# GeckoBreakout.net
KiCad netlist of a schematic drawn in Altium Designer
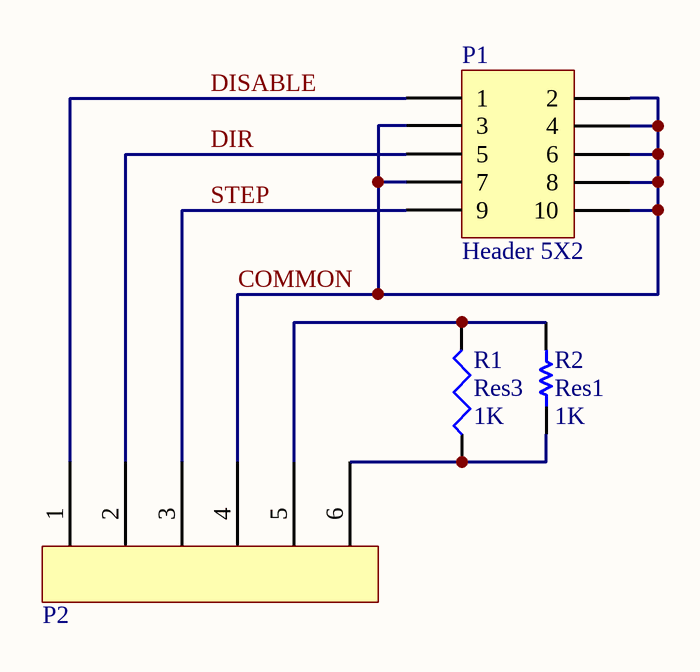
[diagram p0: GeckoBreakout.SchDoc]

(export (version "E")
  (design (tool "Eeschema 10.0.6"))
  (components
    (comp (ref "P1")
      (value "Header 5X2")
      (footprint "BETTER HDR2X5")
      (description "Header, 5-Pin, Dual row")
      (fields (field (name "PUBLISHER") "Altium Limited"))
      (libsource (lib "Miscellaneous Connectors") (part "Header 5X2"))
    )
    (comp (ref "P2")
      (value "Phoenix_1933228")
      (footprint "Phoenix_1933228")
      (libsource (lib "GechoBreakout") (part "Phoenix_1933228"))
    )
    (comp (ref "R1")
      (value "Res3")
      (footprint "3216[1206]")
      (description "Resistor")
      (fields (field (name "ALTIUM_VALUE") "1K") (field (name "PUBLISHER") "Altium Limited"))
      (libsource (lib "Miscellaneous Devices") (part "Res3"))
    )
    (comp (ref "R2")
      (value "Res1")
      (footprint "AXIAL-0.4")
      (description "Resistor")
      (fields (field (name "ALTIUM_VALUE") "1K") (field (name "PUBLISHER") "Altium Limited"))
      (libsource (lib "Miscellaneous Devices") (part "Res1"))
    )
  )
  (nets
    (net (code "1") (name "/COMMON") (class "Default")
      (node (ref "P1") (pin "10") (pinfunction "10_10") (pintype "passive"))
      (node (ref "P1") (pin "2") (pinfunction "2_2") (pintype "passive"))
      (node (ref "P1") (pin "3") (pinfunction "3_3") (pintype "passive"))
      (node (ref "P1") (pin "4") (pinfunction "4_4") (pintype "passive"))
      (node (ref "P1") (pin "6") (pinfunction "6_6") (pintype "passive"))
      (node (ref "P1") (pin "7") (pinfunction "7_7") (pintype "passive"))
      (node (ref "P1") (pin "8") (pinfunction "8_8") (pintype "passive"))
      (node (ref "P2") (pin "4") (pinfunction "4_4") (pintype "passive"))
    )
    (net (code "2") (name "/DIR") (class "Default")
      (node (ref "P1") (pin "5") (pinfunction "5_5") (pintype "passive"))
      (node (ref "P2") (pin "2") (pinfunction "2_2") (pintype "passive"))
    )
    (net (code "3") (name "/DISABLE") (class "Default")
      (node (ref "P1") (pin "1") (pinfunction "1_1") (pintype "passive"))
      (node (ref "P2") (pin "1") (pinfunction "1_1") (pintype "passive"))
    )
    (net (code "4") (name "/STEP") (class "Default")
      (node (ref "P1") (pin "9") (pinfunction "9_9") (pintype "passive"))
      (node (ref "P2") (pin "3") (pinfunction "3_3") (pintype "passive"))
    )
    (net (code "5") (name "Net-(P2-Pad5)") (class "Default")
      (node (ref "P2") (pin "5") (pinfunction "5_5") (pintype "passive"))
      (node (ref "R1") (pin "2") (pinfunction "2_2") (pintype "passive"))
      (node (ref "R2") (pin "2") (pinfunction "2_2") (pintype "passive"))
    )
    (net (code "6") (name "Net-(P2-Pad6)") (class "Default")
      (node (ref "P2") (pin "6") (pinfunction "6_6") (pintype "passive"))
      (node (ref "R1") (pin "1") (pinfunction "1_1") (pintype "passive"))
      (node (ref "R2") (pin "1") (pinfunction "1_1") (pintype "passive"))
    )
  )
)
